# FPGA2.net
KiCad netlist of a schematic drawn in Altium Designer
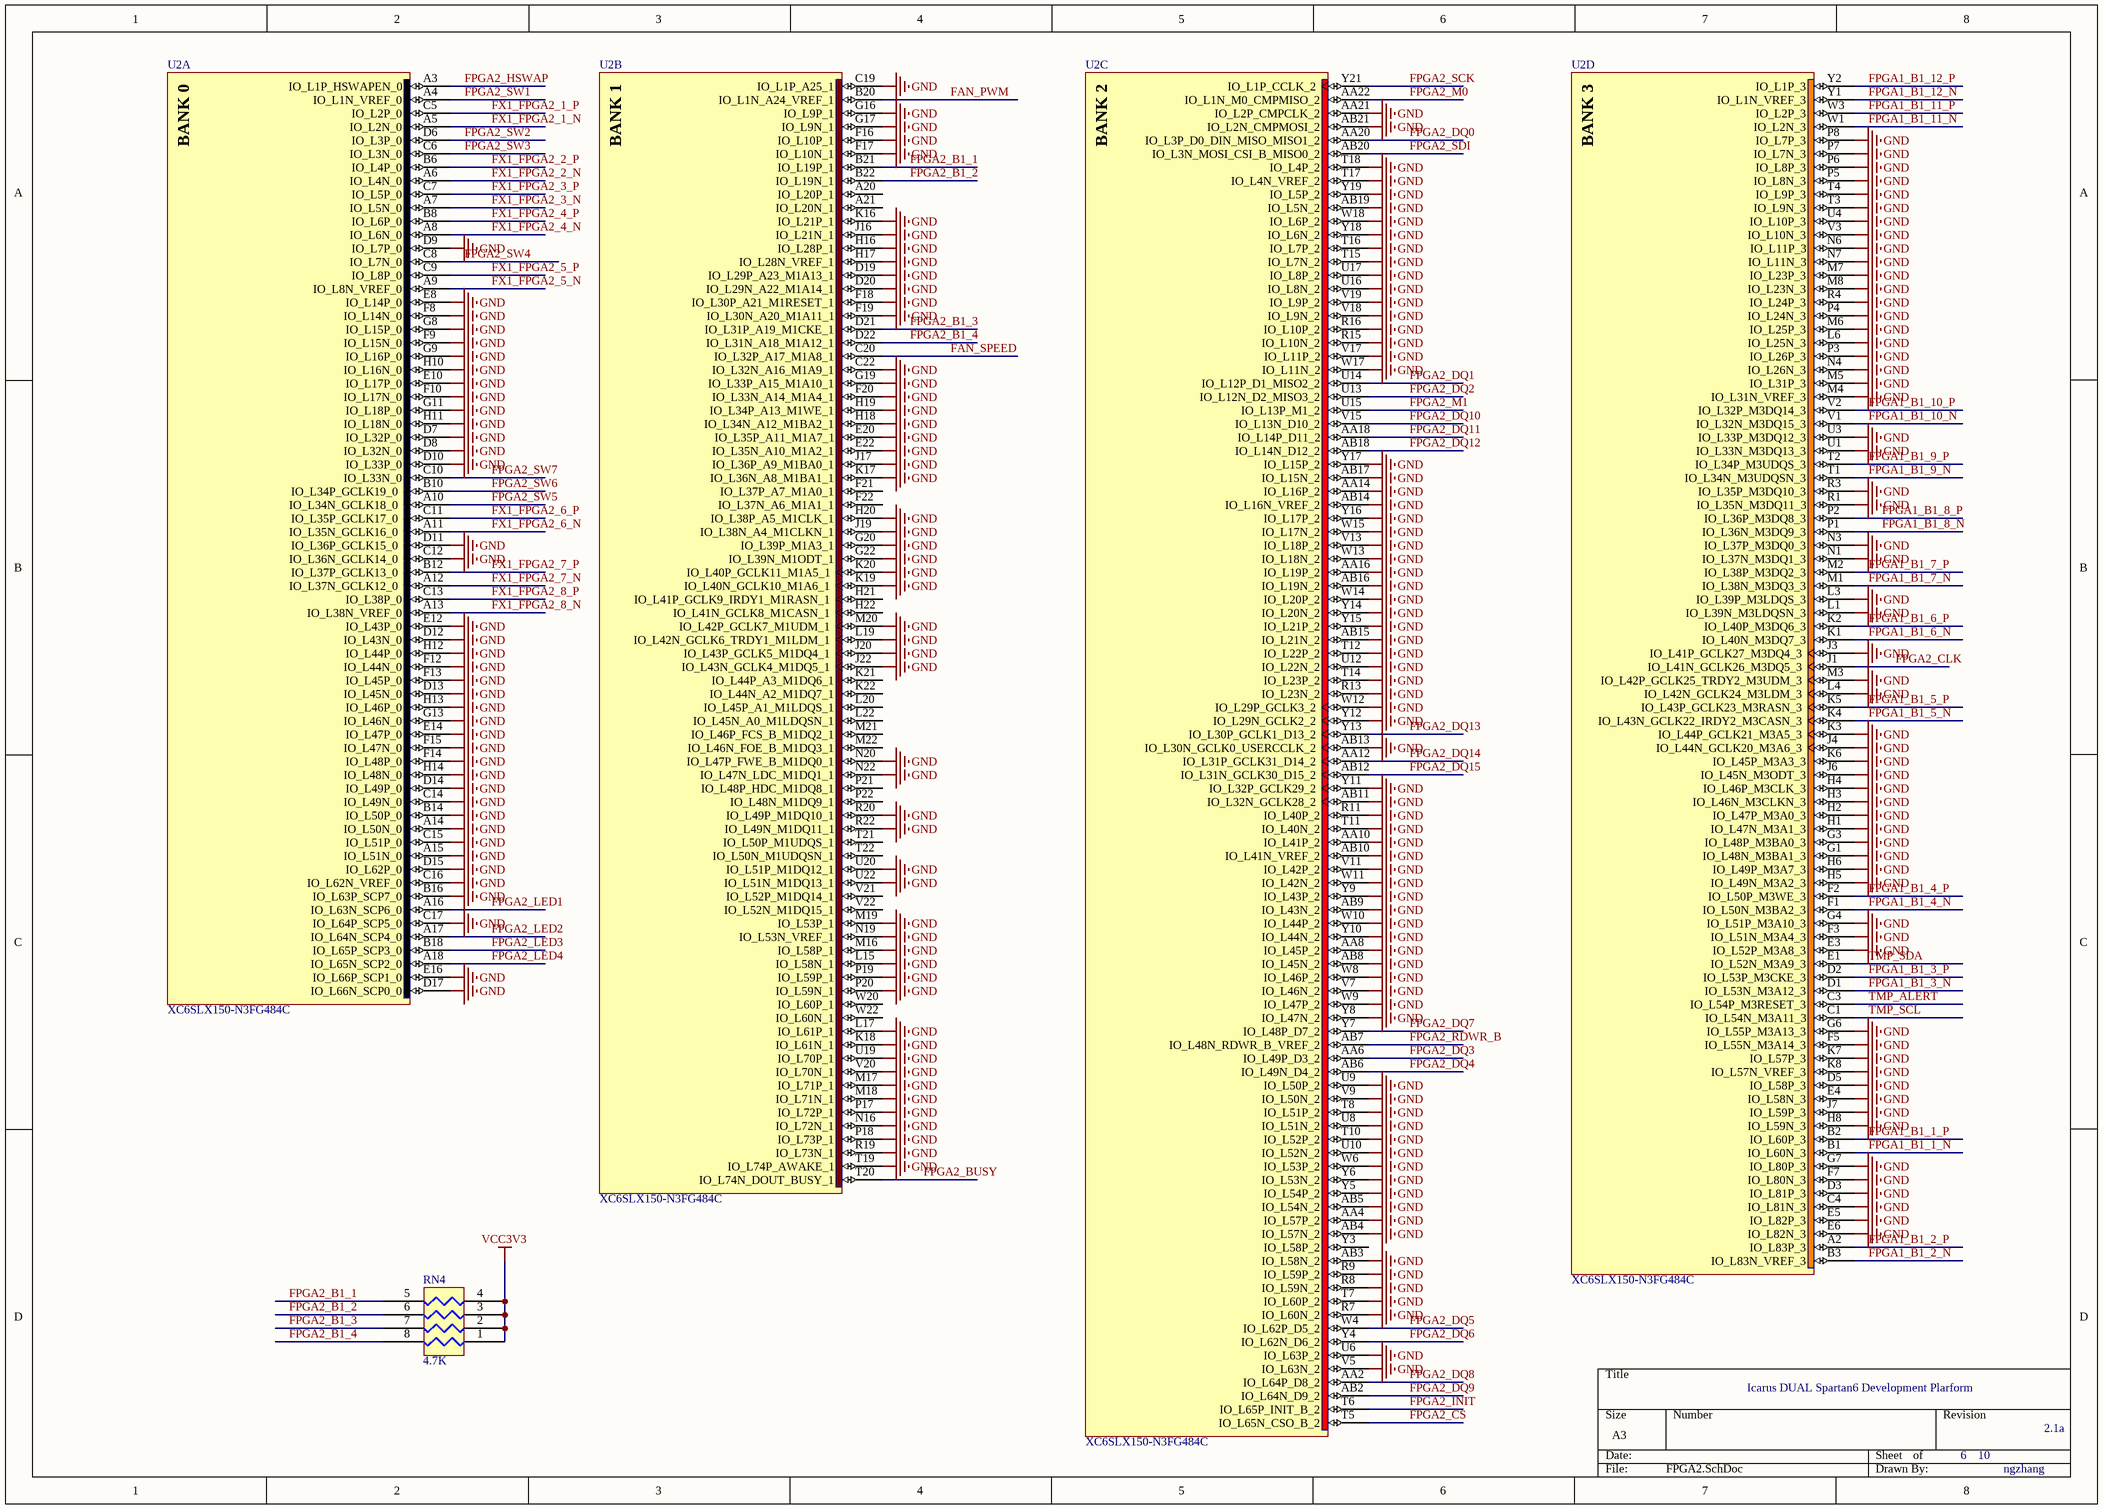
[diagram p0: FPGA2.SchDoc]

(export (version "E")
  (design (tool "Eeschema 10.0.6"))
  (components
    (comp (ref "RN4") (value "4.7K") (footprint "EXBV8V") (libsource (lib "S6") (part "RES4PACK")))
    (comp (ref "U2")
      (value "XC6SLX150-N3FG484C")
      (footprint "FG484")
      (fields (field (name "PUBLISHER") "Altium Limited"))
      (libsource (lib "Xilinx Spartan-6") (part "XC6SLX150-N3FG484C"))
    )
  )
  (nets
    (net (code "1") (name "/FAN_PWM") (class "Default")
      (node (ref "U2") (pin "B20") (pinfunction "IO_L1N_A24_VREF_1_B20") (pintype "bidirectional"))
    )
    (net (code "2") (name "/FAN_SPEED") (class "Default")
      (node (ref "U2") (pin "C20") (pinfunction "IO_L32P_A17_M1A8_1_C20") (pintype "bidirectional"))
    )
    (net (code "3") (name "/FPGA1_B1_1_N") (class "Default")
      (node (ref "U2") (pin "B1") (pinfunction "IO_L60N_3_B1") (pintype "bidirectional"))
    )
    (net (code "4") (name "/FPGA1_B1_1_P") (class "Default")
      (node (ref "U2") (pin "B2") (pinfunction "IO_L60P_3_B2") (pintype "bidirectional"))
    )
    (net (code "5") (name "/FPGA1_B1_2_N") (class "Default")
      (node (ref "U2") (pin "B3") (pinfunction "IO_L83N_VREF_3_B3") (pintype "bidirectional"))
    )
    (net (code "6") (name "/FPGA1_B1_2_P") (class "Default")
      (node (ref "U2") (pin "A2") (pinfunction "IO_L83P_3_A2") (pintype "bidirectional"))
    )
    (net (code "7") (name "/FPGA1_B1_3_N") (class "Default")
      (node (ref "U2") (pin "D1") (pinfunction "IO_L53N_M3A12_3_D1") (pintype "bidirectional"))
    )
    (net (code "8") (name "/FPGA1_B1_3_P") (class "Default")
      (node (ref "U2") (pin "D2") (pinfunction "IO_L53P_M3CKE_3_D2") (pintype "bidirectional"))
    )
    (net (code "9") (name "/FPGA1_B1_4_N") (class "Default")
      (node (ref "U2") (pin "F1") (pinfunction "IO_L50N_M3BA2_3_F1") (pintype "bidirectional"))
    )
    (net (code "10") (name "/FPGA1_B1_4_P") (class "Default")
      (node (ref "U2") (pin "F2") (pinfunction "IO_L50P_M3WE_3_F2") (pintype "bidirectional"))
    )
    (net (code "11") (name "/FPGA1_B1_5_N") (class "Default")
      (node (ref "U2") (pin "K4") (pinfunction "IO_L43N_GCLK22_IRDY2_M3CASN_3_K4") (pintype "bidirectional"))
    )
    (net (code "12") (name "/FPGA1_B1_5_P") (class "Default")
      (node (ref "U2") (pin "K5") (pinfunction "IO_L43P_GCLK23_M3RASN_3_K5") (pintype "bidirectional"))
    )
    (net (code "13") (name "/FPGA1_B1_6_N") (class "Default")
      (node (ref "U2") (pin "K1") (pinfunction "IO_L40N_M3DQ7_3_K1") (pintype "bidirectional"))
    )
    (net (code "14") (name "/FPGA1_B1_6_P") (class "Default")
      (node (ref "U2") (pin "K2") (pinfunction "IO_L40P_M3DQ6_3_K2") (pintype "bidirectional"))
    )
    (net (code "15") (name "/FPGA1_B1_7_N") (class "Default")
      (node (ref "U2") (pin "M1") (pinfunction "IO_L38N_M3DQ3_3_M1") (pintype "bidirectional"))
    )
    (net (code "16") (name "/FPGA1_B1_7_P") (class "Default")
      (node (ref "U2") (pin "M2") (pinfunction "IO_L38P_M3DQ2_3_M2") (pintype "bidirectional"))
    )
    (net (code "17") (name "/FPGA1_B1_8_N") (class "Default")
      (node (ref "U2") (pin "P1") (pinfunction "IO_L36N_M3DQ9_3_P1") (pintype "bidirectional"))
    )
    (net (code "18") (name "/FPGA1_B1_8_P") (class "Default")
      (node (ref "U2") (pin "P2") (pinfunction "IO_L36P_M3DQ8_3_P2") (pintype "bidirectional"))
    )
    (net (code "19") (name "/FPGA1_B1_9_N") (class "Default")
      (node (ref "U2") (pin "T1") (pinfunction "IO_L34N_M3UDQSN_3_T1") (pintype "bidirectional"))
    )
    (net (code "20") (name "/FPGA1_B1_9_P") (class "Default")
      (node (ref "U2") (pin "T2") (pinfunction "IO_L34P_M3UDQS_3_T2") (pintype "bidirectional"))
    )
    (net (code "21") (name "/FPGA1_B1_10_N") (class "Default")
      (node (ref "U2") (pin "V1") (pinfunction "IO_L32N_M3DQ15_3_V1") (pintype "bidirectional"))
    )
    (net (code "22") (name "/FPGA1_B1_10_P") (class "Default")
      (node (ref "U2") (pin "V2") (pinfunction "IO_L32P_M3DQ14_3_V2") (pintype "bidirectional"))
    )
    (net (code "23") (name "/FPGA1_B1_11_N") (class "Default")
      (node (ref "U2") (pin "W1") (pinfunction "IO_L2N_3_W1") (pintype "bidirectional"))
    )
    (net (code "24") (name "/FPGA1_B1_11_P") (class "Default")
      (node (ref "U2") (pin "W3") (pinfunction "IO_L2P_3_W3") (pintype "bidirectional"))
    )
    (net (code "25") (name "/FPGA1_B1_12_N") (class "Default")
      (node (ref "U2") (pin "Y1") (pinfunction "IO_L1N_VREF_3_Y1") (pintype "bidirectional"))
    )
    (net (code "26") (name "/FPGA1_B1_12_P") (class "Default")
      (node (ref "U2") (pin "Y2") (pinfunction "IO_L1P_3_Y2") (pintype "bidirectional"))
    )
    (net (code "27") (name "/FPGA2_B1_1") (class "Default")
      (node (ref "RN4") (pin "5") (pinfunction "5_5") (pintype "power_in"))
      (node (ref "U2") (pin "B21") (pinfunction "IO_L19P_1_B21") (pintype "bidirectional"))
    )
    (net (code "28") (name "/FPGA2_B1_2") (class "Default")
      (node (ref "RN4") (pin "6") (pinfunction "6_6") (pintype "power_in"))
      (node (ref "U2") (pin "B22") (pinfunction "IO_L19N_1_B22") (pintype "bidirectional"))
    )
    (net (code "29") (name "/FPGA2_B1_3") (class "Default")
      (node (ref "RN4") (pin "7") (pinfunction "7_7") (pintype "power_in"))
      (node (ref "U2") (pin "D21") (pinfunction "IO_L31P_A19_M1CKE_1_D21") (pintype "bidirectional"))
    )
    (net (code "30") (name "/FPGA2_B1_4") (class "Default")
      (node (ref "RN4") (pin "8") (pinfunction "8_8") (pintype "power_in"))
      (node (ref "U2") (pin "D22") (pinfunction "IO_L31N_A18_M1A12_1_D22") (pintype "bidirectional"))
    )
    (net (code "31") (name "/FPGA2_BUSY") (class "Default")
      (node (ref "U2") (pin "T20") (pinfunction "IO_L74N_DOUT_BUSY_1_T20") (pintype "bidirectional"))
    )
    (net (code "32") (name "/FPGA2_CLK") (class "Default")
      (node (ref "U2") (pin "J1") (pinfunction "IO_L41N_GCLK26_M3DQ5_3_J1") (pintype "bidirectional"))
    )
    (net (code "33") (name "/FPGA2_CS") (class "Default")
      (node (ref "U2") (pin "T5") (pinfunction "IO_L65N_CSO_B_2_T5") (pintype "bidirectional"))
    )
    (net (code "34") (name "/FPGA2_DQ0") (class "Default")
      (node (ref "U2") (pin "AA20") (pinfunction "IO_L3P_D0_DIN_MISO_MISO1_2_AA20") (pintype "bidirectional"))
    )
    (net (code "35") (name "/FPGA2_DQ1") (class "Default")
      (node (ref "U2") (pin "U14") (pinfunction "IO_L12P_D1_MISO2_2_U14") (pintype "bidirectional"))
    )
    (net (code "36") (name "/FPGA2_DQ2") (class "Default")
      (node (ref "U2") (pin "U13") (pinfunction "IO_L12N_D2_MISO3_2_U13") (pintype "bidirectional"))
    )
    (net (code "37") (name "/FPGA2_DQ3") (class "Default")
      (node (ref "U2") (pin "AA6") (pinfunction "IO_L49P_D3_2_AA6") (pintype "bidirectional"))
    )
    (net (code "38") (name "/FPGA2_DQ4") (class "Default")
      (node (ref "U2") (pin "AB6") (pinfunction "IO_L49N_D4_2_AB6") (pintype "bidirectional"))
    )
    (net (code "39") (name "/FPGA2_DQ5") (class "Default")
      (node (ref "U2") (pin "W4") (pinfunction "IO_L62P_D5_2_W4") (pintype "bidirectional"))
    )
    (net (code "40") (name "/FPGA2_DQ6") (class "Default")
      (node (ref "U2") (pin "Y4") (pinfunction "IO_L62N_D6_2_Y4") (pintype "bidirectional"))
    )
    (net (code "41") (name "/FPGA2_DQ7") (class "Default")
      (node (ref "U2") (pin "Y7") (pinfunction "IO_L48P_D7_2_Y7") (pintype "bidirectional"))
    )
    (net (code "42") (name "/FPGA2_DQ8") (class "Default")
      (node (ref "U2") (pin "AA2") (pinfunction "IO_L64P_D8_2_AA2") (pintype "bidirectional"))
    )
    (net (code "43") (name "/FPGA2_DQ9") (class "Default")
      (node (ref "U2") (pin "AB2") (pinfunction "IO_L64N_D9_2_AB2") (pintype "bidirectional"))
    )
    (net (code "44") (name "/FPGA2_DQ10") (class "Default")
      (node (ref "U2") (pin "V15") (pinfunction "IO_L13N_D10_2_V15") (pintype "bidirectional"))
    )
    (net (code "45") (name "/FPGA2_DQ11") (class "Default")
      (node (ref "U2") (pin "AA18") (pinfunction "IO_L14P_D11_2_AA18") (pintype "bidirectional"))
    )
    (net (code "46") (name "/FPGA2_DQ12") (class "Default")
      (node (ref "U2") (pin "AB18") (pinfunction "IO_L14N_D12_2_AB18") (pintype "bidirectional"))
    )
    (net (code "47") (name "/FPGA2_DQ13") (class "Default")
      (node (ref "U2") (pin "Y13") (pinfunction "IO_L30P_GCLK1_D13_2_Y13") (pintype "bidirectional"))
    )
    (net (code "48") (name "/FPGA2_DQ14") (class "Default")
      (node (ref "U2") (pin "AA12") (pinfunction "IO_L31P_GCLK31_D14_2_AA12") (pintype "bidirectional"))
    )
    (net (code "49") (name "/FPGA2_DQ15") (class "Default")
      (node (ref "U2") (pin "AB12") (pinfunction "IO_L31N_GCLK30_D15_2_AB12") (pintype "bidirectional"))
    )
    (net (code "50") (name "/FPGA2_HSWAP") (class "Default")
      (node (ref "U2") (pin "A3") (pinfunction "IO_L1P_HSWAPEN_0_A3") (pintype "bidirectional"))
    )
    (net (code "51") (name "/FPGA2_INIT") (class "Default")
      (node (ref "U2") (pin "T6") (pinfunction "IO_L65P_INIT_B_2_T6") (pintype "bidirectional"))
    )
    (net (code "52") (name "/FPGA2_LED1") (class "Default")
      (node (ref "U2") (pin "A16") (pinfunction "IO_L63N_SCP6_0_A16") (pintype "bidirectional"))
    )
    (net (code "53") (name "/FPGA2_LED2") (class "Default")
      (node (ref "U2") (pin "A17") (pinfunction "IO_L64N_SCP4_0_A17") (pintype "bidirectional"))
    )
    (net (code "54") (name "/FPGA2_LED3") (class "Default")
      (node (ref "U2") (pin "B18") (pinfunction "IO_L65P_SCP3_0_B18") (pintype "bidirectional"))
    )
    (net (code "55") (name "/FPGA2_LED4") (class "Default")
      (node (ref "U2") (pin "A18") (pinfunction "IO_L65N_SCP2_0_A18") (pintype "bidirectional"))
    )
    (net (code "56") (name "/FPGA2_M0") (class "Default")
      (node (ref "U2") (pin "AA22") (pinfunction "IO_L1N_M0_CMPMISO_2_AA22") (pintype "bidirectional"))
    )
    (net (code "57") (name "/FPGA2_M1") (class "Default")
      (node (ref "U2") (pin "U15") (pinfunction "IO_L13P_M1_2_U15") (pintype "bidirectional"))
    )
    (net (code "58") (name "/FPGA2_RDWR_B") (class "Default")
      (node (ref "U2") (pin "AB7") (pinfunction "IO_L48N_RDWR_B_VREF_2_AB7") (pintype "bidirectional"))
    )
    (net (code "59") (name "/FPGA2_SCK") (class "Default")
      (node (ref "U2") (pin "Y21") (pinfunction "IO_L1P_CCLK_2_Y21") (pintype "bidirectional"))
    )
    (net (code "60") (name "/FPGA2_SDI") (class "Default")
      (node (ref "U2") (pin "AB20") (pinfunction "IO_L3N_MOSI_CSI_B_MISO0_2_AB20") (pintype "bidirectional"))
    )
    (net (code "61") (name "/FPGA2_SW1") (class "Default")
      (node (ref "U2") (pin "A4") (pinfunction "IO_L1N_VREF_0_A4") (pintype "bidirectional"))
    )
    (net (code "62") (name "/FPGA2_SW2") (class "Default")
      (node (ref "U2") (pin "D6") (pinfunction "IO_L3P_0_D6") (pintype "bidirectional"))
    )
    (net (code "63") (name "/FPGA2_SW3") (class "Default")
      (node (ref "U2") (pin "C6") (pinfunction "IO_L3N_0_C6") (pintype "bidirectional"))
    )
    (net (code "64") (name "/FPGA2_SW4") (class "Default")
      (node (ref "U2") (pin "C8") (pinfunction "IO_L7N_0_C8") (pintype "bidirectional"))
    )
    (net (code "65") (name "/FPGA2_SW5") (class "Default")
      (node (ref "U2") (pin "A10") (pinfunction "IO_L34N_GCLK18_0_A10") (pintype "bidirectional"))
    )
    (net (code "66") (name "/FPGA2_SW6") (class "Default")
      (node (ref "U2") (pin "B10") (pinfunction "IO_L34P_GCLK19_0_B10") (pintype "bidirectional"))
    )
    (net (code "67") (name "/FPGA2_SW7") (class "Default")
      (node (ref "U2") (pin "C10") (pinfunction "IO_L33N_0_C10") (pintype "bidirectional"))
    )
    (net (code "68") (name "/FX1_FPGA2_1_N") (class "Default")
      (node (ref "U2") (pin "A5") (pinfunction "IO_L2N_0_A5") (pintype "bidirectional"))
    )
    (net (code "69") (name "/FX1_FPGA2_1_P") (class "Default")
      (node (ref "U2") (pin "C5") (pinfunction "IO_L2P_0_C5") (pintype "bidirectional"))
    )
    (net (code "70") (name "/FX1_FPGA2_2_N") (class "Default")
      (node (ref "U2") (pin "A6") (pinfunction "IO_L4N_0_A6") (pintype "bidirectional"))
    )
    (net (code "71") (name "/FX1_FPGA2_2_P") (class "Default")
      (node (ref "U2") (pin "B6") (pinfunction "IO_L4P_0_B6") (pintype "bidirectional"))
    )
    (net (code "72") (name "/FX1_FPGA2_3_N") (class "Default")
      (node (ref "U2") (pin "A7") (pinfunction "IO_L5N_0_A7") (pintype "bidirectional"))
    )
    (net (code "73") (name "/FX1_FPGA2_3_P") (class "Default")
      (node (ref "U2") (pin "C7") (pinfunction "IO_L5P_0_C7") (pintype "bidirectional"))
    )
    (net (code "74") (name "/FX1_FPGA2_4_N") (class "Default")
      (node (ref "U2") (pin "A8") (pinfunction "IO_L6N_0_A8") (pintype "bidirectional"))
    )
    (net (code "75") (name "/FX1_FPGA2_4_P") (class "Default")
      (node (ref "U2") (pin "B8") (pinfunction "IO_L6P_0_B8") (pintype "bidirectional"))
    )
    (net (code "76") (name "/FX1_FPGA2_5_N") (class "Default")
      (node (ref "U2") (pin "A9") (pinfunction "IO_L8N_VREF_0_A9") (pintype "bidirectional"))
    )
    (net (code "77") (name "/FX1_FPGA2_5_P") (class "Default")
      (node (ref "U2") (pin "C9") (pinfunction "IO_L8P_0_C9") (pintype "bidirectional"))
    )
    (net (code "78") (name "/FX1_FPGA2_6_N") (class "Default")
      (node (ref "U2") (pin "A11") (pinfunction "IO_L35N_GCLK16_0_A11") (pintype "bidirectional"))
    )
    (net (code "79") (name "/FX1_FPGA2_6_P") (class "Default")
      (node (ref "U2") (pin "C11") (pinfunction "IO_L35P_GCLK17_0_C11") (pintype "bidirectional"))
    )
    (net (code "80") (name "/FX1_FPGA2_7_N") (class "Default")
      (node (ref "U2") (pin "A12") (pinfunction "IO_L37N_GCLK12_0_A12") (pintype "bidirectional"))
    )
    (net (code "81") (name "/FX1_FPGA2_7_P") (class "Default")
      (node (ref "U2") (pin "B12") (pinfunction "IO_L37P_GCLK13_0_B12") (pintype "bidirectional"))
    )
    (net (code "82") (name "/FX1_FPGA2_8_N") (class "Default")
      (node (ref "U2") (pin "A13") (pinfunction "IO_L38N_VREF_0_A13") (pintype "bidirectional"))
    )
    (net (code "83") (name "/FX1_FPGA2_8_P") (class "Default")
      (node (ref "U2") (pin "C13") (pinfunction "IO_L38P_0_C13") (pintype "bidirectional"))
    )
    (net (code "84") (name "/TMP_ALERT") (class "Default")
      (node (ref "U2") (pin "C3") (pinfunction "IO_L54P_M3RESET_3_C3") (pintype "bidirectional"))
    )
    (net (code "85") (name "/TMP_SCL") (class "Default")
      (node (ref "U2") (pin "C1") (pinfunction "IO_L54N_M3A11_3_C1") (pintype "bidirectional"))
    )
    (net (code "86") (name "/TMP_SDA") (class "Default")
      (node (ref "U2") (pin "E1") (pinfunction "IO_L52N_M3A9_3_E1") (pintype "bidirectional"))
    )
    (net (code "87") (name "GND") (class "Default")
      (node (ref "U2") (pin "A14") (pinfunction "IO_L50N_0_A14") (pintype "bidirectional"))
      (node (ref "U2") (pin "A15") (pinfunction "IO_L51N_0_A15") (pintype "bidirectional"))
      (node (ref "U2") (pin "AA10") (pinfunction "IO_L41P_2_AA10") (pintype "bidirectional"))
      (node (ref "U2") (pin "AA14") (pinfunction "IO_L16P_2_AA14") (pintype "bidirectional"))
      (node (ref "U2") (pin "AA16") (pinfunction "IO_L19P_2_AA16") (pintype "bidirectional"))
      (node (ref "U2") (pin "AA21") (pinfunction "IO_L2P_CMPCLK_2_AA21") (pintype "bidirectional"))
      (node (ref "U2") (pin "AA4") (pinfunction "IO_L57P_2_AA4") (pintype "bidirectional"))
      (node (ref "U2") (pin "AA8") (pinfunction "IO_L45P_2_AA8") (pintype "bidirectional"))
      (node (ref "U2") (pin "AB10") (pinfunction "IO_L41N_VREF_2_AB10") (pintype "bidirectional"))
      (node (ref "U2") (pin "AB11") (pinfunction "IO_L32N_GCLK28_2_AB11") (pintype "bidirectional"))
      (node (ref "U2") (pin "AB13") (pinfunction "IO_L30N_GCLK0_USERCCLK_2_AB13") (pintype "bidirectional"))
      (node (ref "U2") (pin "AB14") (pinfunction "IO_L16N_VREF_2_AB14") (pintype "bidirectional"))
      (node (ref "U2") (pin "AB15") (pinfunction "IO_L21N_2_AB15") (pintype "bidirectional"))
      (node (ref "U2") (pin "AB16") (pinfunction "IO_L19N_2_AB16") (pintype "bidirectional"))
      (node (ref "U2") (pin "AB17") (pinfunction "IO_L15N_2_AB17") (pintype "bidirectional"))
      (node (ref "U2") (pin "AB19") (pinfunction "IO_L5N_2_AB19") (pintype "bidirectional"))
      (node (ref "U2") (pin "AB21") (pinfunction "IO_L2N_CMPMOSI_2_AB21") (pintype "bidirectional"))
      (node (ref "U2") (pin "AB3") (pinfunction "IO_L58N_2_AB3") (pintype "bidirectional"))
      (node (ref "U2") (pin "AB4") (pinfunction "IO_L57N_2_AB4") (pintype "bidirectional"))
      (node (ref "U2") (pin "AB5") (pinfunction "IO_L54N_2_AB5") (pintype "bidirectional"))
      (node (ref "U2") (pin "AB8") (pinfunction "IO_L45N_2_AB8") (pintype "bidirectional"))
      (node (ref "U2") (pin "AB9") (pinfunction "IO_L43N_2_AB9") (pintype "bidirectional"))
      (node (ref "U2") (pin "B14") (pinfunction "IO_L50P_0_B14") (pintype "bidirectional"))
      (node (ref "U2") (pin "B16") (pinfunction "IO_L63P_SCP7_0_B16") (pintype "bidirectional"))
      (node (ref "U2") (pin "C12") (pinfunction "IO_L36N_GCLK14_0_C12") (pintype "bidirectional"))
      (node (ref "U2") (pin "C14") (pinfunction "IO_L49N_0_C14") (pintype "bidirectional"))
      (node (ref "U2") (pin "C15") (pinfunction "IO_L51P_0_C15") (pintype "bidirectional"))
      (node (ref "U2") (pin "C16") (pinfunction "IO_L62N_VREF_0_C16") (pintype "bidirectional"))
      (node (ref "U2") (pin "C17") (pinfunction "IO_L64P_SCP5_0_C17") (pintype "bidirectional"))
      (node (ref "U2") (pin "C19") (pinfunction "IO_L1P_A25_1_C19") (pintype "bidirectional"))
      (node (ref "U2") (pin "C22") (pinfunction "IO_L32N_A16_M1A9_1_C22") (pintype "bidirectional"))
      (node (ref "U2") (pin "C4") (pinfunction "IO_L81N_3_C4") (pintype "bidirectional"))
      (node (ref "U2") (pin "D10") (pinfunction "IO_L33P_0_D10") (pintype "bidirectional"))
      (node (ref "U2") (pin "D11") (pinfunction "IO_L36P_GCLK15_0_D11") (pintype "bidirectional"))
      (node (ref "U2") (pin "D12") (pinfunction "IO_L43N_0_D12") (pintype "bidirectional"))
      (node (ref "U2") (pin "D13") (pinfunction "IO_L45N_0_D13") (pintype "bidirectional"))
      (node (ref "U2") (pin "D14") (pinfunction "IO_L49P_0_D14") (pintype "bidirectional"))
      (node (ref "U2") (pin "D15") (pinfunction "IO_L62P_0_D15") (pintype "bidirectional"))
      (node (ref "U2") (pin "D17") (pinfunction "IO_L66N_SCP0_0_D17") (pintype "bidirectional"))
      (node (ref "U2") (pin "D19") (pinfunction "IO_L29P_A23_M1A13_1_D19") (pintype "bidirectional"))
      (node (ref "U2") (pin "D20") (pinfunction "IO_L29N_A22_M1A14_1_D20") (pintype "bidirectional"))
      (node (ref "U2") (pin "D3") (pinfunction "IO_L81P_3_D3") (pintype "bidirectional"))
      (node (ref "U2") (pin "D5") (pinfunction "IO_L58P_3_D5") (pintype "bidirectional"))
      (node (ref "U2") (pin "D7") (pinfunction "IO_L32P_0_D7") (pintype "bidirectional"))
      (node (ref "U2") (pin "D8") (pinfunction "IO_L32N_0_D8") (pintype "bidirectional"))
      (node (ref "U2") (pin "D9") (pinfunction "IO_L7P_0_D9") (pintype "bidirectional"))
      (node (ref "U2") (pin "E10") (pinfunction "IO_L17P_0_E10") (pintype "bidirectional"))
      (node (ref "U2") (pin "E12") (pinfunction "IO_L43P_0_E12") (pintype "bidirectional"))
      (node (ref "U2") (pin "E14") (pinfunction "IO_L47P_0_E14") (pintype "bidirectional"))
      (node (ref "U2") (pin "E16") (pinfunction "IO_L66P_SCP1_0_E16") (pintype "bidirectional"))
      (node (ref "U2") (pin "E20") (pinfunction "IO_L35P_A11_M1A7_1_E20") (pintype "bidirectional"))
      (node (ref "U2") (pin "E22") (pinfunction "IO_L35N_A10_M1A2_1_E22") (pintype "bidirectional"))
      (node (ref "U2") (pin "E3") (pinfunction "IO_L52P_M3A8_3_E3") (pintype "bidirectional"))
      (node (ref "U2") (pin "E4") (pinfunction "IO_L58N_3_E4") (pintype "bidirectional"))
      (node (ref "U2") (pin "E5") (pinfunction "IO_L82P_3_E5") (pintype "bidirectional"))
      (node (ref "U2") (pin "E6") (pinfunction "IO_L82N_3_E6") (pintype "bidirectional"))
      (node (ref "U2") (pin "E8") (pinfunction "IO_L14P_0_E8") (pintype "bidirectional"))
      (node (ref "U2") (pin "F10") (pinfunction "IO_L17N_0_F10") (pintype "bidirectional"))
      (node (ref "U2") (pin "F12") (pinfunction "IO_L44N_0_F12") (pintype "bidirectional"))
      (node (ref "U2") (pin "F13") (pinfunction "IO_L45P_0_F13") (pintype "bidirectional"))
      (node (ref "U2") (pin "F14") (pinfunction "IO_L48P_0_F14") (pintype "bidirectional"))
      (node (ref "U2") (pin "F15") (pinfunction "IO_L47N_0_F15") (pintype "bidirectional"))
      (node (ref "U2") (pin "F16") (pinfunction "IO_L10P_1_F16") (pintype "bidirectional"))
      (node (ref "U2") (pin "F17") (pinfunction "IO_L10N_1_F17") (pintype "bidirectional"))
      (node (ref "U2") (pin "F18") (pinfunction "IO_L30P_A21_M1RESET_1_F18") (pintype "bidirectional"))
      (node (ref "U2") (pin "F19") (pinfunction "IO_L30N_A20_M1A11_1_F19") (pintype "bidirectional"))
      (node (ref "U2") (pin "F20") (pinfunction "IO_L33N_A14_M1A4_1_F20") (pintype "bidirectional"))
      (node (ref "U2") (pin "F3") (pinfunction "IO_L51N_M3A4_3_F3") (pintype "bidirectional"))
      (node (ref "U2") (pin "F5") (pinfunction "IO_L55N_M3A14_3_F5") (pintype "bidirectional"))
      (node (ref "U2") (pin "F7") (pinfunction "IO_L80N_3_F7") (pintype "bidirectional"))
      (node (ref "U2") (pin "F8") (pinfunction "IO_L14N_0_F8") (pintype "bidirectional"))
      (node (ref "U2") (pin "F9") (pinfunction "IO_L15N_0_F9") (pintype "bidirectional"))
      (node (ref "U2") (pin "G1") (pinfunction "IO_L48N_M3BA1_3_G1") (pintype "bidirectional"))
      (node (ref "U2") (pin "G11") (pinfunction "IO_L18P_0_G11") (pintype "bidirectional"))
      (node (ref "U2") (pin "G13") (pinfunction "IO_L46N_0_G13") (pintype "bidirectional"))
      (node (ref "U2") (pin "G16") (pinfunction "IO_L9P_1_G16") (pintype "bidirectional"))
      (node (ref "U2") (pin "G17") (pinfunction "IO_L9N_1_G17") (pintype "bidirectional"))
      (node (ref "U2") (pin "G19") (pinfunction "IO_L33P_A15_M1A10_1_G19") (pintype "bidirectional"))
      (node (ref "U2") (pin "G20") (pinfunction "IO_L39P_M1A3_1_G20") (pintype "bidirectional"))
      (node (ref "U2") (pin "G22") (pinfunction "IO_L39N_M1ODT_1_G22") (pintype "bidirectional"))
      (node (ref "U2") (pin "G3") (pinfunction "IO_L48P_M3BA0_3_G3") (pintype "bidirectional"))
      (node (ref "U2") (pin "G4") (pinfunction "IO_L51P_M3A10_3_G4") (pintype "bidirectional"))
      (node (ref "U2") (pin "G6") (pinfunction "IO_L55P_M3A13_3_G6") (pintype "bidirectional"))
      (node (ref "U2") (pin "G7") (pinfunction "IO_L80P_3_G7") (pintype "bidirectional"))
      (node (ref "U2") (pin "G8") (pinfunction "IO_L15P_0_G8") (pintype "bidirectional"))
      (node (ref "U2") (pin "G9") (pinfunction "IO_L16P_0_G9") (pintype "bidirectional"))
      (node (ref "U2") (pin "H1") (pinfunction "IO_L47N_M3A1_3_H1") (pintype "bidirectional"))
      (node (ref "U2") (pin "H10") (pinfunction "IO_L16N_0_H10") (pintype "bidirectional"))
      (node (ref "U2") (pin "H11") (pinfunction "IO_L18N_0_H11") (pintype "bidirectional"))
      (node (ref "U2") (pin "H12") (pinfunction "IO_L44P_0_H12") (pintype "bidirectional"))
      (node (ref "U2") (pin "H13") (pinfunction "IO_L46P_0_H13") (pintype "bidirectional"))
      (node (ref "U2") (pin "H14") (pinfunction "IO_L48N_0_H14") (pintype "bidirectional"))
      (node (ref "U2") (pin "H16") (pinfunction "IO_L28P_1_H16") (pintype "bidirectional"))
      (node (ref "U2") (pin "H17") (pinfunction "IO_L28N_VREF_1_H17") (pintype "bidirectional"))
      (node (ref "U2") (pin "H18") (pinfunction "IO_L34N_A12_M1BA2_1_H18") (pintype "bidirectional"))
      (node (ref "U2") (pin "H19") (pinfunction "IO_L34P_A13_M1WE_1_H19") (pintype "bidirectional"))
      (node (ref "U2") (pin "H2") (pinfunction "IO_L47P_M3A0_3_H2") (pintype "bidirectional"))
      (node (ref "U2") (pin "H20") (pinfunction "IO_L38P_A5_M1CLK_1_H20") (pintype "bidirectional"))
      (node (ref "U2") (pin "H3") (pinfunction "IO_L46N_M3CLKN_3_H3") (pintype "bidirectional"))
      (node (ref "U2") (pin "H4") (pinfunction "IO_L46P_M3CLK_3_H4") (pintype "bidirectional"))
      (node (ref "U2") (pin "H5") (pinfunction "IO_L49N_M3A2_3_H5") (pintype "bidirectional"))
      (node (ref "U2") (pin "H6") (pinfunction "IO_L49P_M3A7_3_H6") (pintype "bidirectional"))
      (node (ref "U2") (pin "H8") (pinfunction "IO_L59N_3_H8") (pintype "bidirectional"))
      (node (ref "U2") (pin "J16") (pinfunction "IO_L21N_1_J16") (pintype "bidirectional"))
      (node (ref "U2") (pin "J17") (pinfunction "IO_L36P_A9_M1BA0_1_J17") (pintype "bidirectional"))
      (node (ref "U2") (pin "J19") (pinfunction "IO_L38N_A4_M1CLKN_1_J19") (pintype "bidirectional"))
      (node (ref "U2") (pin "J20") (pinfunction "IO_L43P_GCLK5_M1DQ4_1_J20") (pintype "bidirectional"))
      (node (ref "U2") (pin "J22") (pinfunction "IO_L43N_GCLK4_M1DQ5_1_J22") (pintype "bidirectional"))
      (node (ref "U2") (pin "J3") (pinfunction "IO_L41P_GCLK27_M3DQ4_3_J3") (pintype "bidirectional"))
      (node (ref "U2") (pin "J4") (pinfunction "IO_L44N_GCLK20_M3A6_3_J4") (pintype "bidirectional"))
      (node (ref "U2") (pin "J6") (pinfunction "IO_L45N_M3ODT_3_J6") (pintype "bidirectional"))
      (node (ref "U2") (pin "J7") (pinfunction "IO_L59P_3_J7") (pintype "bidirectional"))
      (node (ref "U2") (pin "K16") (pinfunction "IO_L21P_1_K16") (pintype "bidirectional"))
      (node (ref "U2") (pin "K17") (pinfunction "IO_L36N_A8_M1BA1_1_K17") (pintype "bidirectional"))
      (node (ref "U2") (pin "K18") (pinfunction "IO_L61N_1_K18") (pintype "bidirectional"))
      (node (ref "U2") (pin "K19") (pinfunction "IO_L40N_GCLK10_M1A6_1_K19") (pintype "bidirectional"))
      (node (ref "U2") (pin "K20") (pinfunction "IO_L40P_GCLK11_M1A5_1_K20") (pintype "bidirectional"))
      (node (ref "U2") (pin "K3") (pinfunction "IO_L44P_GCLK21_M3A5_3_K3") (pintype "bidirectional"))
      (node (ref "U2") (pin "K6") (pinfunction "IO_L45P_M3A3_3_K6") (pintype "bidirectional"))
      (node (ref "U2") (pin "K7") (pinfunction "IO_L57P_3_K7") (pintype "bidirectional"))
      (node (ref "U2") (pin "K8") (pinfunction "IO_L57N_VREF_3_K8") (pintype "bidirectional"))
      (node (ref "U2") (pin "L1") (pinfunction "IO_L39N_M3LDQSN_3_L1") (pintype "bidirectional"))
      (node (ref "U2") (pin "L15") (pinfunction "IO_L58N_1_L15") (pintype "bidirectional"))
      (node (ref "U2") (pin "L17") (pinfunction "IO_L61P_1_L17") (pintype "bidirectional"))
      (node (ref "U2") (pin "L19") (pinfunction "IO_L42N_GCLK6_TRDY1_M1LDM_1_L19") (pintype "bidirectional"))
      (node (ref "U2") (pin "L3") (pinfunction "IO_L39P_M3LDQS_3_L3") (pintype "bidirectional"))
      (node (ref "U2") (pin "L4") (pinfunction "IO_L42N_GCLK24_M3LDM_3_L4") (pintype "bidirectional"))
      (node (ref "U2") (pin "L6") (pinfunction "IO_L25N_3_L6") (pintype "bidirectional"))
      (node (ref "U2") (pin "M16") (pinfunction "IO_L58P_1_M16") (pintype "bidirectional"))
      (node (ref "U2") (pin "M17") (pinfunction "IO_L71P_1_M17") (pintype "bidirectional"))
      (node (ref "U2") (pin "M18") (pinfunction "IO_L71N_1_M18") (pintype "bidirectional"))
      (node (ref "U2") (pin "M19") (pinfunction "IO_L53P_1_M19") (pintype "bidirectional"))
      (node (ref "U2") (pin "M20") (pinfunction "IO_L42P_GCLK7_M1UDM_1_M20") (pintype "bidirectional"))
      (node (ref "U2") (pin "M3") (pinfunction "IO_L42P_GCLK25_TRDY2_M3UDM_3_M3") (pintype "bidirectional"))
      (node (ref "U2") (pin "M4") (pinfunction "IO_L31N_VREF_3_M4") (pintype "bidirectional"))
      (node (ref "U2") (pin "M5") (pinfunction "IO_L31P_3_M5") (pintype "bidirectional"))
      (node (ref "U2") (pin "M6") (pinfunction "IO_L25P_3_M6") (pintype "bidirectional"))
      (node (ref "U2") (pin "M7") (pinfunction "IO_L23P_3_M7") (pintype "bidirectional"))
      (node (ref "U2") (pin "M8") (pinfunction "IO_L23N_3_M8") (pintype "bidirectional"))
      (node (ref "U2") (pin "N1") (pinfunction "IO_L37N_M3DQ1_3_N1") (pintype "bidirectional"))
      (node (ref "U2") (pin "N16") (pinfunction "IO_L72N_1_N16") (pintype "bidirectional"))
      (node (ref "U2") (pin "N19") (pinfunction "IO_L53N_VREF_1_N19") (pintype "bidirectional"))
      (node (ref "U2") (pin "N20") (pinfunction "IO_L47P_FWE_B_M1DQ0_1_N20") (pintype "bidirectional"))
      (node (ref "U2") (pin "N22") (pinfunction "IO_L47N_LDC_M1DQ1_1_N22") (pintype "bidirectional"))
      (node (ref "U2") (pin "N3") (pinfunction "IO_L37P_M3DQ0_3_N3") (pintype "bidirectional"))
      (node (ref "U2") (pin "N4") (pinfunction "IO_L26N_3_N4") (pintype "bidirectional"))
      (node (ref "U2") (pin "N6") (pinfunction "IO_L11P_3_N6") (pintype "bidirectional"))
      (node (ref "U2") (pin "N7") (pinfunction "IO_L11N_3_N7") (pintype "bidirectional"))
      (node (ref "U2") (pin "P17") (pinfunction "IO_L72P_1_P17") (pintype "bidirectional"))
      (node (ref "U2") (pin "P18") (pinfunction "IO_L73P_1_P18") (pintype "bidirectional"))
      (node (ref "U2") (pin "P19") (pinfunction "IO_L59P_1_P19") (pintype "bidirectional"))
      (node (ref "U2") (pin "P20") (pinfunction "IO_L59N_1_P20") (pintype "bidirectional"))
      (node (ref "U2") (pin "P3") (pinfunction "IO_L26P_3_P3") (pintype "bidirectional"))
      (node (ref "U2") (pin "P4") (pinfunction "IO_L24N_3_P4") (pintype "bidirectional"))
      (node (ref "U2") (pin "P5") (pinfunction "IO_L8N_3_P5") (pintype "bidirectional"))
      (node (ref "U2") (pin "P6") (pinfunction "IO_L8P_3_P6") (pintype "bidirectional"))
      (node (ref "U2") (pin "P7") (pinfunction "IO_L7N_3_P7") (pintype "bidirectional"))
      (node (ref "U2") (pin "P8") (pinfunction "IO_L7P_3_P8") (pintype "bidirectional"))
      (node (ref "U2") (pin "R1") (pinfunction "IO_L35N_M3DQ11_3_R1") (pintype "bidirectional"))
      (node (ref "U2") (pin "R11") (pinfunction "IO_L40P_2_R11") (pintype "bidirectional"))
      (node (ref "U2") (pin "R13") (pinfunction "IO_L23N_2_R13") (pintype "bidirectional"))
      (node (ref "U2") (pin "R15") (pinfunction "IO_L10N_2_R15") (pintype "bidirectional"))
      (node (ref "U2") (pin "R16") (pinfunction "IO_L10P_2_R16") (pintype "bidirectional"))
      (node (ref "U2") (pin "R19") (pinfunction "IO_L73N_1_R19") (pintype "bidirectional"))
      (node (ref "U2") (pin "R20") (pinfunction "IO_L49P_M1DQ10_1_R20") (pintype "bidirectional"))
      (node (ref "U2") (pin "R22") (pinfunction "IO_L49N_M1DQ11_1_R22") (pintype "bidirectional"))
      (node (ref "U2") (pin "R3") (pinfunction "IO_L35P_M3DQ10_3_R3") (pintype "bidirectional"))
      (node (ref "U2") (pin "R4") (pinfunction "IO_L24P_3_R4") (pintype "bidirectional"))
      (node (ref "U2") (pin "R7") (pinfunction "IO_L60N_2_R7") (pintype "bidirectional"))
      (node (ref "U2") (pin "R8") (pinfunction "IO_L59N_2_R8") (pintype "bidirectional"))
      (node (ref "U2") (pin "R9") (pinfunction "IO_L59P_2_R9") (pintype "bidirectional"))
      (node (ref "U2") (pin "T10") (pinfunction "IO_L52P_2_T10") (pintype "bidirectional"))
      (node (ref "U2") (pin "T11") (pinfunction "IO_L40N_2_T11") (pintype "bidirectional"))
      (node (ref "U2") (pin "T12") (pinfunction "IO_L22P_2_T12") (pintype "bidirectional"))
      (node (ref "U2") (pin "T14") (pinfunction "IO_L23P_2_T14") (pintype "bidirectional"))
      (node (ref "U2") (pin "T15") (pinfunction "IO_L7N_2_T15") (pintype "bidirectional"))
      (node (ref "U2") (pin "T16") (pinfunction "IO_L7P_2_T16") (pintype "bidirectional"))
      (node (ref "U2") (pin "T17") (pinfunction "IO_L4N_VREF_2_T17") (pintype "bidirectional"))
      (node (ref "U2") (pin "T18") (pinfunction "IO_L4P_2_T18") (pintype "bidirectional"))
      (node (ref "U2") (pin "T19") (pinfunction "IO_L74P_AWAKE_1_T19") (pintype "bidirectional"))
      (node (ref "U2") (pin "T3") (pinfunction "IO_L9N_3_T3") (pintype "bidirectional"))
      (node (ref "U2") (pin "T4") (pinfunction "IO_L9P_3_T4") (pintype "bidirectional"))
      (node (ref "U2") (pin "T7") (pinfunction "IO_L60P_2_T7") (pintype "bidirectional"))
      (node (ref "U2") (pin "T8") (pinfunction "IO_L51P_2_T8") (pintype "bidirectional"))
      (node (ref "U2") (pin "U1") (pinfunction "IO_L33N_M3DQ13_3_U1") (pintype "bidirectional"))
      (node (ref "U2") (pin "U10") (pinfunction "IO_L52N_2_U10") (pintype "bidirectional"))
      (node (ref "U2") (pin "U12") (pinfunction "IO_L22N_2_U12") (pintype "bidirectional"))
      (node (ref "U2") (pin "U16") (pinfunction "IO_L8N_2_U16") (pintype "bidirectional"))
      (node (ref "U2") (pin "U17") (pinfunction "IO_L8P_2_U17") (pintype "bidirectional"))
      (node (ref "U2") (pin "U19") (pinfunction "IO_L70P_1_U19") (pintype "bidirectional"))
      (node (ref "U2") (pin "U20") (pinfunction "IO_L51P_M1DQ12_1_U20") (pintype "bidirectional"))
      (node (ref "U2") (pin "U22") (pinfunction "IO_L51N_M1DQ13_1_U22") (pintype "bidirectional"))
      (node (ref "U2") (pin "U3") (pinfunction "IO_L33P_M3DQ12_3_U3") (pintype "bidirectional"))
      (node (ref "U2") (pin "U4") (pinfunction "IO_L10P_3_U4") (pintype "bidirectional"))
      (node (ref "U2") (pin "U6") (pinfunction "IO_L63P_2_U6") (pintype "bidirectional"))
      (node (ref "U2") (pin "U8") (pinfunction "IO_L51N_2_U8") (pintype "bidirectional"))
      (node (ref "U2") (pin "U9") (pinfunction "IO_L50P_2_U9") (pintype "bidirectional"))
      (node (ref "U2") (pin "V11") (pinfunction "IO_L42P_2_V11") (pintype "bidirectional"))
      (node (ref "U2") (pin "V13") (pinfunction "IO_L18P_2_V13") (pintype "bidirectional"))
      (node (ref "U2") (pin "V17") (pinfunction "IO_L11P_2_V17") (pintype "bidirectional"))
      (node (ref "U2") (pin "V18") (pinfunction "IO_L9N_2_V18") (pintype "bidirectional"))
      (node (ref "U2") (pin "V19") (pinfunction "IO_L9P_2_V19") (pintype "bidirectional"))
      (node (ref "U2") (pin "V20") (pinfunction "IO_L70N_1_V20") (pintype "bidirectional"))
      (node (ref "U2") (pin "V3") (pinfunction "IO_L10N_3_V3") (pintype "bidirectional"))
      (node (ref "U2") (pin "V5") (pinfunction "IO_L63N_2_V5") (pintype "bidirectional"))
      (node (ref "U2") (pin "V7") (pinfunction "IO_L46N_2_V7") (pintype "bidirectional"))
      (node (ref "U2") (pin "V9") (pinfunction "IO_L50N_2_V9") (pintype "bidirectional"))
      (node (ref "U2") (pin "W10") (pinfunction "IO_L44P_2_W10") (pintype "bidirectional"))
      (node (ref "U2") (pin "W11") (pinfunction "IO_L42N_2_W11") (pintype "bidirectional"))
      (node (ref "U2") (pin "W12") (pinfunction "IO_L29P_GCLK3_2_W12") (pintype "bidirectional"))
      (node (ref "U2") (pin "W13") (pinfunction "IO_L18N_2_W13") (pintype "bidirectional"))
      (node (ref "U2") (pin "W14") (pinfunction "IO_L20P_2_W14") (pintype "bidirectional"))
      (node (ref "U2") (pin "W15") (pinfunction "IO_L17N_2_W15") (pintype "bidirectional"))
      (node (ref "U2") (pin "W17") (pinfunction "IO_L11N_2_W17") (pintype "bidirectional"))
      (node (ref "U2") (pin "W18") (pinfunction "IO_L6P_2_W18") (pintype "bidirectional"))
      (node (ref "U2") (pin "W6") (pinfunction "IO_L53P_2_W6") (pintype "bidirectional"))
      (node (ref "U2") (pin "W8") (pinfunction "IO_L46P_2_W8") (pintype "bidirectional"))
      (node (ref "U2") (pin "W9") (pinfunction "IO_L47P_2_W9") (pintype "bidirectional"))
      (node (ref "U2") (pin "Y10") (pinfunction "IO_L44N_2_Y10") (pintype "bidirectional"))
      (node (ref "U2") (pin "Y11") (pinfunction "IO_L32P_GCLK29_2_Y11") (pintype "bidirectional"))
      (node (ref "U2") (pin "Y12") (pinfunction "IO_L29N_GCLK2_2_Y12") (pintype "bidirectional"))
      (node (ref "U2") (pin "Y14") (pinfunction "IO_L20N_2_Y14") (pintype "bidirectional"))
      (node (ref "U2") (pin "Y15") (pinfunction "IO_L21P_2_Y15") (pintype "bidirectional"))
      (node (ref "U2") (pin "Y16") (pinfunction "IO_L17P_2_Y16") (pintype "bidirectional"))
      (node (ref "U2") (pin "Y17") (pinfunction "IO_L15P_2_Y17") (pintype "bidirectional"))
      (node (ref "U2") (pin "Y18") (pinfunction "IO_L6N_2_Y18") (pintype "bidirectional"))
      (node (ref "U2") (pin "Y19") (pinfunction "IO_L5P_2_Y19") (pintype "bidirectional"))
      (node (ref "U2") (pin "Y5") (pinfunction "IO_L54P_2_Y5") (pintype "bidirectional"))
      (node (ref "U2") (pin "Y6") (pinfunction "IO_L53N_2_Y6") (pintype "bidirectional"))
      (node (ref "U2") (pin "Y8") (pinfunction "IO_L47N_2_Y8") (pintype "bidirectional"))
      (node (ref "U2") (pin "Y9") (pinfunction "IO_L43P_2_Y9") (pintype "bidirectional"))
    )
    (net (code "88") (name "VCC3V3") (class "Default")
      (node (ref "RN4") (pin "1") (pinfunction "1_1") (pintype "power_in"))
      (node (ref "RN4") (pin "2") (pinfunction "2_2") (pintype "power_in"))
      (node (ref "RN4") (pin "3") (pinfunction "3_3") (pintype "power_in"))
      (node (ref "RN4") (pin "4") (pinfunction "4_4") (pintype "power_in"))
    )
    (net (code "89") (name "unconnected-(U2B-IO_L20N_1-PadA21)") (class "Default")
      (node (ref "U2") (pin "A21") (pinfunction "IO_L20N_1_A21") (pintype "bidirectional"))
    )
    (net (code "90") (name "unconnected-(U2B-IO_L20P_1-PadA20)") (class "Default")
      (node (ref "U2") (pin "A20") (pinfunction "IO_L20P_1_A20") (pintype "bidirectional"))
    )
    (net (code "91") (name "unconnected-(U2B-IO_L37N_A6_M1A1_1-PadF22)") (class "Default")
      (node (ref "U2") (pin "F22") (pinfunction "IO_L37N_A6_M1A1_1_F22") (pintype "bidirectional"))
    )
    (net (code "92") (name "unconnected-(U2B-IO_L37P_A7_M1A0_1-PadF21)") (class "Default")
      (node (ref "U2") (pin "F21") (pinfunction "IO_L37P_A7_M1A0_1_F21") (pintype "bidirectional"))
    )
    (net (code "93") (name "unconnected-(U2B-IO_L41N_GCLK8_M1CASN_1-PadH22)") (class "Default")
      (node (ref "U2") (pin "H22") (pinfunction "IO_L41N_GCLK8_M1CASN_1_H22") (pintype "bidirectional"))
    )
    (net (code "94") (name "unconnected-(U2B-IO_L41P_GCLK9_IRDY1_M1RASN_1-PadH21)") (class "Default")
      (node (ref "U2") (pin "H21") (pinfunction "IO_L41P_GCLK9_IRDY1_M1RASN_1_H21") (pintype "bidirectional"))
    )
    (net (code "95") (name "unconnected-(U2B-IO_L44N_A2_M1DQ7_1-PadK22)") (class "Default")
      (node (ref "U2") (pin "K22") (pinfunction "IO_L44N_A2_M1DQ7_1_K22") (pintype "bidirectional"))
    )
    (net (code "96") (name "unconnected-(U2B-IO_L44P_A3_M1DQ6_1-PadK21)") (class "Default")
      (node (ref "U2") (pin "K21") (pinfunction "IO_L44P_A3_M1DQ6_1_K21") (pintype "bidirectional"))
    )
    (net (code "97") (name "unconnected-(U2B-IO_L45N_A0_M1LDQSN_1-PadL22)") (class "Default")
      (node (ref "U2") (pin "L22") (pinfunction "IO_L45N_A0_M1LDQSN_1_L22") (pintype "bidirectional"))
    )
    (net (code "98") (name "unconnected-(U2B-IO_L45P_A1_M1LDQS_1-PadL20)") (class "Default")
      (node (ref "U2") (pin "L20") (pinfunction "IO_L45P_A1_M1LDQS_1_L20") (pintype "bidirectional"))
    )
    (net (code "99") (name "unconnected-(U2B-IO_L46N_FOE_B_M1DQ3_1-PadM22)") (class "Default")
      (node (ref "U2") (pin "M22") (pinfunction "IO_L46N_FOE_B_M1DQ3_1_M22") (pintype "bidirectional"))
    )
    (net (code "100") (name "unconnected-(U2B-IO_L46P_FCS_B_M1DQ2_1-PadM21)") (class "Default")
      (node (ref "U2") (pin "M21") (pinfunction "IO_L46P_FCS_B_M1DQ2_1_M21") (pintype "bidirectional"))
    )
    (net (code "101") (name "unconnected-(U2B-IO_L48N_M1DQ9_1-PadP22)") (class "Default")
      (node (ref "U2") (pin "P22") (pinfunction "IO_L48N_M1DQ9_1_P22") (pintype "bidirectional"))
    )
    (net (code "102") (name "unconnected-(U2B-IO_L48P_HDC_M1DQ8_1-PadP21)") (class "Default")
      (node (ref "U2") (pin "P21") (pinfunction "IO_L48P_HDC_M1DQ8_1_P21") (pintype "bidirectional"))
    )
    (net (code "103") (name "unconnected-(U2B-IO_L50N_M1UDQSN_1-PadT22)") (class "Default")
      (node (ref "U2") (pin "T22") (pinfunction "IO_L50N_M1UDQSN_1_T22") (pintype "bidirectional"))
    )
    (net (code "104") (name "unconnected-(U2B-IO_L50P_M1UDQS_1-PadT21)") (class "Default")
      (node (ref "U2") (pin "T21") (pinfunction "IO_L50P_M1UDQS_1_T21") (pintype "bidirectional"))
    )
    (net (code "105") (name "unconnected-(U2B-IO_L52N_M1DQ15_1-PadV22)") (class "Default")
      (node (ref "U2") (pin "V22") (pinfunction "IO_L52N_M1DQ15_1_V22") (pintype "bidirectional"))
    )
    (net (code "106") (name "unconnected-(U2B-IO_L52P_M1DQ14_1-PadV21)") (class "Default")
      (node (ref "U2") (pin "V21") (pinfunction "IO_L52P_M1DQ14_1_V21") (pintype "bidirectional"))
    )
    (net (code "107") (name "unconnected-(U2B-IO_L60N_1-PadW22)") (class "Default")
      (node (ref "U2") (pin "W22") (pinfunction "IO_L60N_1_W22") (pintype "bidirectional"))
    )
    (net (code "108") (name "unconnected-(U2B-IO_L60P_1-PadW20)") (class "Default")
      (node (ref "U2") (pin "W20") (pinfunction "IO_L60P_1_W20") (pintype "bidirectional"))
    )
    (net (code "109") (name "unconnected-(U2C-IO_L58P_2-PadY3)") (class "Default")
      (node (ref "U2") (pin "Y3") (pinfunction "IO_L58P_2_Y3") (pintype "bidirectional"))
    )
  )
)
